# Diagram_Power.net
KiCad netlist of a schematic drawn in Altium Designer
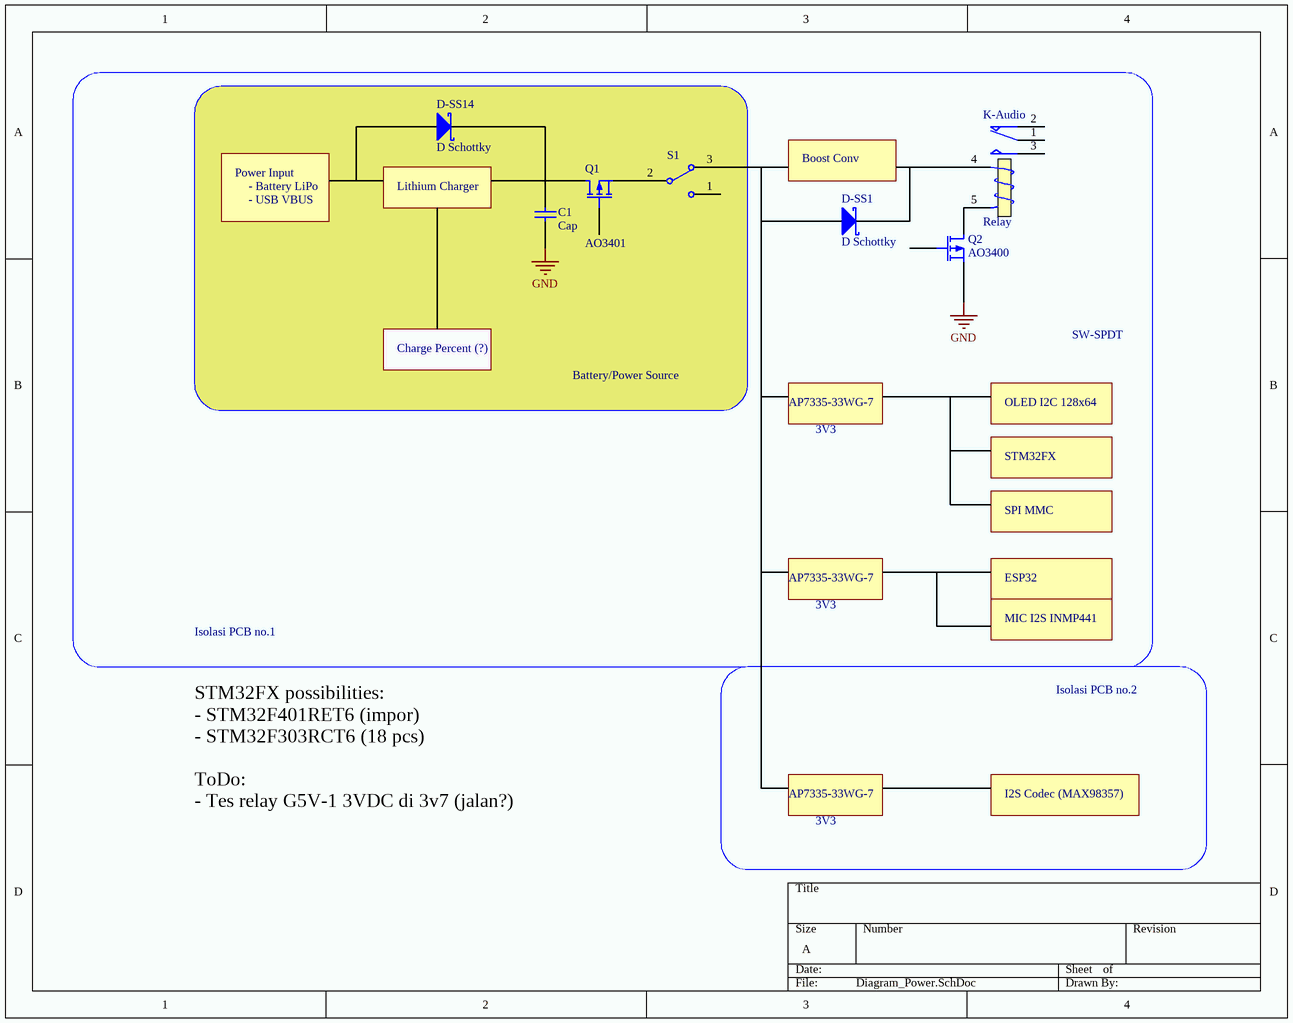
[diagram p0: Diagram_Power.SchDoc]

(export (version "E")
  (design (tool "Eeschema 10.0.6"))
  (components
    (comp (ref "C1")
      (value "Cap")
      (footprint "RAD-0.3")
      (description "Capacitor")
      (fields (field (name "PUBLISHER") "Altium Limited"))
      (libsource (lib "Miscellaneous Devices") (part "Cap"))
    )
    (comp (ref "D-SS1")
      (value "D Schottky")
      (footprint "SMB")
      (description "Schottky Diode")
      (fields (field (name "PUBLISHER") "Altium Limited"))
      (libsource (lib "Miscellaneous Devices") (part "D Schottky"))
    )
    (comp (ref "D-SS14")
      (value "D Schottky")
      (footprint "SMB")
      (description "Schottky Diode")
      (fields (field (name "PUBLISHER") "Altium Limited"))
      (libsource (lib "Miscellaneous Devices") (part "D Schottky"))
    )
    (comp (ref "K-Audio")
      (value "Relay")
      (footprint "MODULE5B")
      (description "SPDT Relay")
      (fields (field (name "PUBLISHER") "Altium Limited"))
      (libsource (lib "Miscellaneous Devices") (part "Relay"))
    )
    (comp (ref "Q1")
      (value "AO3401")
      (footprint "E3")
      (description "P-Channel MOSFET")
      (fields (field (name "PUBLISHER") "Altium Limited"))
      (libsource (lib "Miscellaneous Devices") (part "MOSFET-P"))
    )
    (comp (ref "Q2")
      (value "AO3400")
      (footprint "E3")
      (description "P-Channel MOSFET")
      (fields (field (name "PUBLISHER") "Altium Limited"))
      (libsource (lib "Miscellaneous Devices") (part "MOSFET-P"))
    )
    (comp (ref "S1")
      (value "SW-SPDT")
      (footprint "TL36WW15050")
      (description "SPDT Subminiature Toggle Switch, Right Angle Mounting, Vertical Actuation")
      (fields (field (name "PUBLISHER") "Altium Limited"))
      (libsource (lib "Miscellaneous Devices") (part "SW-SPDT"))
    )
  )
  (nets
    (net (code "2") (name "Net-(K-Audio-T2)") (class "Default")
      (node (ref "K-Audio") (pin "5") (pinfunction "T2_5") (pintype "passive"))
      (node (ref "Q2") (pin "1") (pinfunction "D_1") (pintype "passive"))
    )
    (net (code "3") (name "Net-(Q1-S)") (class "Default")
      (node (ref "Q1") (pin "3") (pinfunction "S_3") (pintype "passive"))
      (node (ref "S1") (pin "2") (pinfunction "2_2") (pintype "passive"))
    )
    (net (code "4") (name "unconnected-(C1-Pad1)") (class "Default")
      (node (ref "C1") (pin "1") (pinfunction "1_1") (pintype "passive"))
    )
    (net (code "5") (name "unconnected-(C1-Pad2)") (class "Default")
      (node (ref "C1") (pin "2") (pinfunction "2_2") (pintype "passive"))
    )
    (net (code "6") (name "unconnected-(D-SS1-A-Pad1)") (class "Default")
      (node (ref "D-SS1") (pin "1") (pinfunction "A_1") (pintype "passive"))
    )
    (net (code "7") (name "unconnected-(D-SS1-K-Pad2)") (class "Default")
      (node (ref "D-SS1") (pin "2") (pinfunction "K_2") (pintype "passive"))
    )
    (net (code "8") (name "unconnected-(D-SS14-A-Pad1)") (class "Default")
      (node (ref "D-SS14") (pin "1") (pinfunction "A_1") (pintype "passive"))
    )
    (net (code "9") (name "unconnected-(D-SS14-K-Pad2)") (class "Default")
      (node (ref "D-SS14") (pin "2") (pinfunction "K_2") (pintype "passive"))
    )
    (net (code "10") (name "unconnected-(K-Audio-COM-Pad1)") (class "Default")
      (node (ref "K-Audio") (pin "1") (pinfunction "COM_1") (pintype "passive"))
    )
    (net (code "11") (name "unconnected-(K-Audio-NC-Pad2)") (class "Default")
      (node (ref "K-Audio") (pin "2") (pinfunction "NC_2") (pintype "passive"))
    )
    (net (code "12") (name "unconnected-(K-Audio-NO-Pad3)") (class "Default")
      (node (ref "K-Audio") (pin "3") (pinfunction "NO_3") (pintype "passive"))
    )
    (net (code "13") (name "unconnected-(K-Audio-T1-Pad4)") (class "Default")
      (node (ref "K-Audio") (pin "4") (pinfunction "T1_4") (pintype "passive"))
    )
    (net (code "14") (name "unconnected-(Q1-D-Pad1)") (class "Default")
      (node (ref "Q1") (pin "1") (pinfunction "D_1") (pintype "passive"))
    )
    (net (code "15") (name "unconnected-(Q1-G-Pad2)") (class "Default")
      (node (ref "Q1") (pin "2") (pinfunction "G_2") (pintype "passive"))
    )
    (net (code "16") (name "unconnected-(Q2-G-Pad2)") (class "Default")
      (node (ref "Q2") (pin "2") (pinfunction "G_2") (pintype "passive"))
    )
    (net (code "17") (name "unconnected-(Q2-S-Pad3)") (class "Default")
      (node (ref "Q2") (pin "3") (pinfunction "S_3") (pintype "passive"))
    )
    (net (code "18") (name "unconnected-(S1-Pad1)") (class "Default")
      (node (ref "S1") (pin "1") (pinfunction "1_1") (pintype "passive"))
    )
    (net (code "19") (name "unconnected-(S1-Pad3)") (class "Default")
      (node (ref "S1") (pin "3") (pinfunction "3_3") (pintype "passive"))
    )
  )
)
